# v4_Controller_PCB.net
KiCad netlist of a schematic drawn in EAGLE
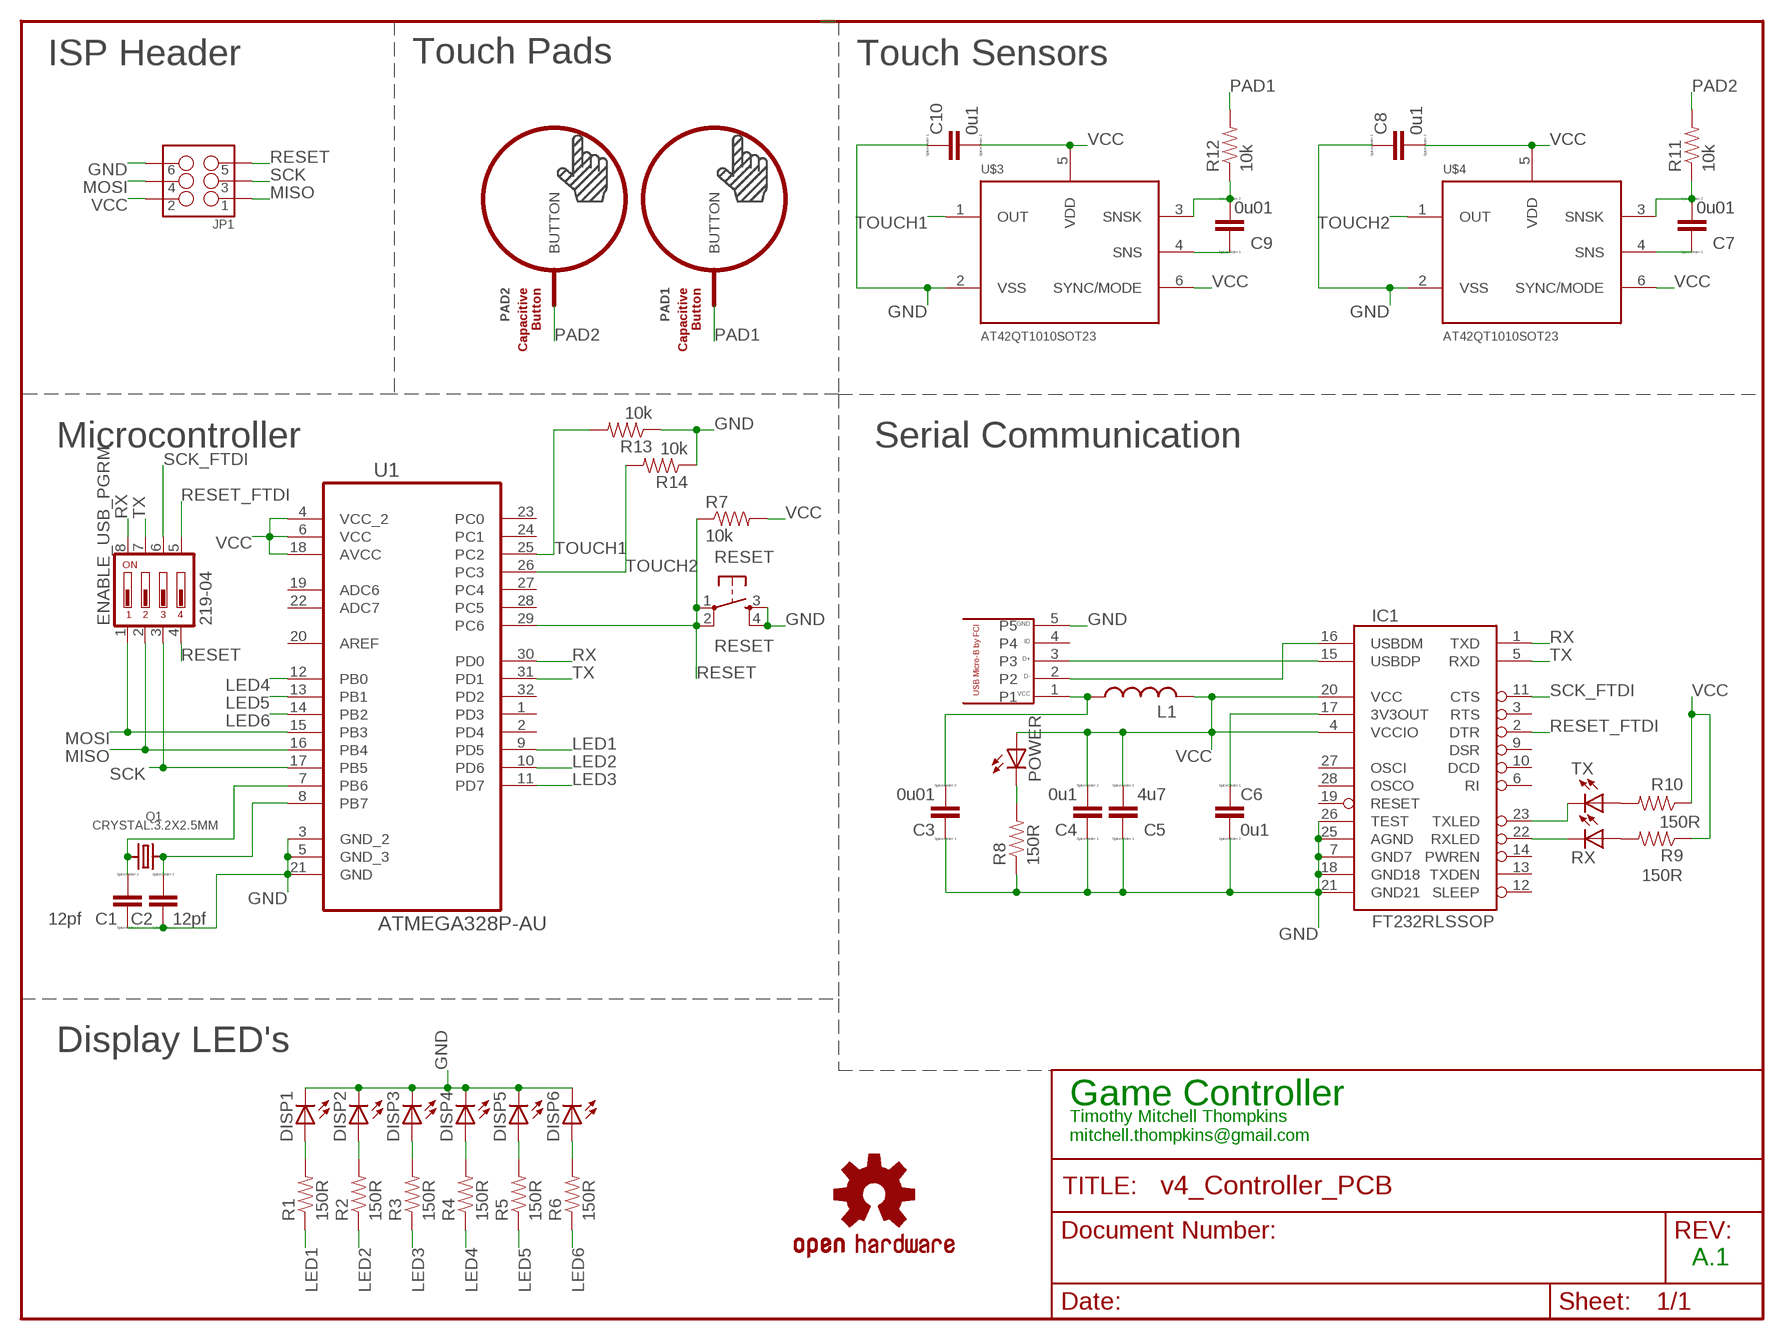
[diagram p0: schematic, sheet 1]

(export (version "E")
  (design (tool "Eeschema 10.0.6"))
  (components
    (comp (ref "BUTTON1")
      (value "TOUCH_LOGO")
      (footprint "eagle-import:TOUCH_LOGO")
      (libsource (lib "eagle-import") (part "TOUCH_LOGO"))
    )
    (comp (ref "C1")
      (value "12pf")
      (footprint "eagle-import:C0603")
      (libsource (lib "eagle-import") (part "CC0603"))
    )
    (comp (ref "C2")
      (value "12pf")
      (footprint "eagle-import:C0603")
      (libsource (lib "eagle-import") (part "CC0603"))
    )
    (comp (ref "C3")
      (value "0u01")
      (footprint "eagle-import:C0603")
      (libsource (lib "eagle-import") (part "CC0603"))
    )
    (comp (ref "C4")
      (value "0u1")
      (footprint "eagle-import:C0603")
      (libsource (lib "eagle-import") (part "CC0603"))
    )
    (comp (ref "C5")
      (value "4u7")
      (footprint "eagle-import:C0603")
      (libsource (lib "eagle-import") (part "CC0603"))
    )
    (comp (ref "C6")
      (value "0u1")
      (footprint "eagle-import:C0603")
      (libsource (lib "eagle-import") (part "CC0603"))
    )
    (comp (ref "C7")
      (value "0u01")
      (footprint "eagle-import:C0603")
      (libsource (lib "eagle-import") (part "CC0603"))
    )
    (comp (ref "C8")
      (value "0u1")
      (footprint "eagle-import:C0603")
      (libsource (lib "eagle-import") (part "CC0603"))
    )
    (comp (ref "C9")
      (value "0u01")
      (footprint "eagle-import:C0603")
      (libsource (lib "eagle-import") (part "CC0603"))
    )
    (comp (ref "C10")
      (value "0u1")
      (footprint "eagle-import:C0603")
      (libsource (lib "eagle-import") (part "CC0603"))
    )
    (comp (ref "DISP1")
      (value "LEDCHIPLED_0603")
      (footprint "eagle-import:CHIPLED_0603")
      (libsource (lib "eagle-import") (part "LEDCHIPLED_0603"))
    )
    (comp (ref "DISP2")
      (value "LEDCHIPLED_0603")
      (footprint "eagle-import:CHIPLED_0603")
      (libsource (lib "eagle-import") (part "LEDCHIPLED_0603"))
    )
    (comp (ref "DISP3")
      (value "LEDCHIPLED_0603")
      (footprint "eagle-import:CHIPLED_0603")
      (libsource (lib "eagle-import") (part "LEDCHIPLED_0603"))
    )
    (comp (ref "DISP4")
      (value "LEDCHIPLED_0603")
      (footprint "eagle-import:CHIPLED_0603")
      (libsource (lib "eagle-import") (part "LEDCHIPLED_0603"))
    )
    (comp (ref "DISP5")
      (value "LEDCHIPLED_0603")
      (footprint "eagle-import:CHIPLED_0603")
      (libsource (lib "eagle-import") (part "LEDCHIPLED_0603"))
    )
    (comp (ref "DISP6")
      (value "LEDCHIPLED_0603")
      (footprint "eagle-import:CHIPLED_0603")
      (libsource (lib "eagle-import") (part "LEDCHIPLED_0603"))
    )
    (comp (ref "ENABLE_USB_PGRM")
      (value "219-04")
      (footprint "eagle-import:CTS-219-04")
      (libsource (lib "eagle-import") (part "219-04"))
    )
    (comp (ref "IC1")
      (value "FT232RLSSOP")
      (footprint "eagle-import:SSOP28DB")
      (libsource (lib "eagle-import") (part "FT232RLSSOP"))
    )
    (comp (ref "JP1")
      (value "M03X2POGO_PINS")
      (footprint "eagle-import:2X3_POGO")
      (libsource (lib "eagle-import") (part "M03X2POGO_PINS"))
    )
    (comp (ref "L1")
      (value "L-USL2012C")
      (footprint "eagle-import:L2012C")
      (libsource (lib "eagle-import") (part "L-USL2012C"))
    )
    (comp (ref "LOGO2")
      (value "OSHW-LOGOS")
      (footprint "eagle-import:OSHW-LOGO-S")
      (libsource (lib "eagle-import") (part "OSHW-LOGOS"))
    )
    (comp (ref "PAD1")
      (value "BUTTON_PASSIVE8MM")
      (footprint "eagle-import:BUTTON_PASSIVE_8MM")
      (libsource (lib "eagle-import") (part "BUTTON_PASSIVE8MM"))
    )
    (comp (ref "PAD2")
      (value "BUTTON_PASSIVE8MM")
      (footprint "eagle-import:BUTTON_PASSIVE_8MM")
      (libsource (lib "eagle-import") (part "BUTTON_PASSIVE8MM"))
    )
    (comp (ref "POWER")
      (value "LEDCHIPLED_0603")
      (footprint "eagle-import:CHIPLED_0603")
      (libsource (lib "eagle-import") (part "LEDCHIPLED_0603"))
    )
    (comp (ref "Q1")
      (value "CRYSTAL.3.2X2.5MM")
      (footprint "eagle-import:3.2X2.5MM")
      (libsource (lib "eagle-import") (part "CRYSTAL.3.2X2.5MM"))
    )
    (comp (ref "R1")
      (value "150R")
      (footprint "eagle-import:0603-RES")
      (libsource (lib "eagle-import") (part "RESISTOR0603-RES"))
    )
    (comp (ref "R2")
      (value "150R")
      (footprint "eagle-import:0603-RES")
      (libsource (lib "eagle-import") (part "RESISTOR0603-RES"))
    )
    (comp (ref "R3")
      (value "150R")
      (footprint "eagle-import:0603-RES")
      (libsource (lib "eagle-import") (part "RESISTOR0603-RES"))
    )
    (comp (ref "R4")
      (value "150R")
      (footprint "eagle-import:0603-RES")
      (libsource (lib "eagle-import") (part "RESISTOR0603-RES"))
    )
    (comp (ref "R5")
      (value "150R")
      (footprint "eagle-import:0603-RES")
      (libsource (lib "eagle-import") (part "RESISTOR0603-RES"))
    )
    (comp (ref "R6")
      (value "150R")
      (footprint "eagle-import:0603-RES")
      (libsource (lib "eagle-import") (part "RESISTOR0603-RES"))
    )
    (comp (ref "R7")
      (value "10k")
      (footprint "eagle-import:0603-RES")
      (libsource (lib "eagle-import") (part "RESISTOR0603-RES"))
    )
    (comp (ref "R8")
      (value "150R")
      (footprint "eagle-import:0603-RES")
      (libsource (lib "eagle-import") (part "RESISTOR0603-RES"))
    )
    (comp (ref "R9")
      (value "150R")
      (footprint "eagle-import:0603-RES")
      (libsource (lib "eagle-import") (part "RESISTOR0603-RES"))
    )
    (comp (ref "R10")
      (value "150R")
      (footprint "eagle-import:0603-RES")
      (libsource (lib "eagle-import") (part "RESISTOR0603-RES"))
    )
    (comp (ref "R11")
      (value "10k")
      (footprint "eagle-import:0603-RES")
      (libsource (lib "eagle-import") (part "RESISTOR0603-RES"))
    )
    (comp (ref "R12")
      (value "10k")
      (footprint "eagle-import:0603-RES")
      (libsource (lib "eagle-import") (part "RESISTOR0603-RES"))
    )
    (comp (ref "R13")
      (value "10k")
      (footprint "eagle-import:0603-RES")
      (libsource (lib "eagle-import") (part "RESISTOR0603-RES"))
    )
    (comp (ref "R14")
      (value "10k")
      (footprint "eagle-import:0603-RES")
      (libsource (lib "eagle-import") (part "RESISTOR0603-RES"))
    )
    (comp (ref "RESET")
      (value "RESET")
      (footprint "eagle-import:TACTILE-PTH")
      (libsource (lib "eagle-import") (part "TAC_SWITCHPTH"))
    )
    (comp (ref "RX")
      (value "LEDCHIPLED_0603")
      (footprint "eagle-import:CHIPLED_0603")
      (libsource (lib "eagle-import") (part "LEDCHIPLED_0603"))
    )
    (comp (ref "TX")
      (value "LEDCHIPLED_0603")
      (footprint "eagle-import:CHIPLED_0603")
      (libsource (lib "eagle-import") (part "LEDCHIPLED_0603"))
    )
    (comp (ref "U$1")
      (value "USB_MICRO_B_FCI")
      (footprint "eagle-import:10118194-0001LF")
      (libsource (lib "eagle-import") (part "USB_MICRO_B_FCI"))
    )
    (comp (ref "U$3")
      (value "AT42QT1010SOT23")
      (footprint "eagle-import:SOT23-6")
      (libsource (lib "eagle-import") (part "AT42QT1010SOT23"))
    )
    (comp (ref "U$4")
      (value "AT42QT1010SOT23")
      (footprint "eagle-import:SOT23-6")
      (libsource (lib "eagle-import") (part "AT42QT1010SOT23"))
    )
    (comp (ref "U$6")
      (value "TOUCH_LOGO")
      (footprint "eagle-import:TOUCH_LOGO")
      (libsource (lib "eagle-import") (part "TOUCH_LOGO"))
    )
    (comp (ref "U1")
      (value "ATMEGA328P-AU")
      (footprint "eagle-import:QFP80P900X900X120-32N")
      (libsource (lib "eagle-import") (part "ATMEGA328P-AU"))
    )
  )
  (nets
    (net (code "1") (name "/GND") (class "Default")
      (node (ref "C1") (pin "1") (pinfunction "1_1") (pintype "passive"))
      (node (ref "C10") (pin "1") (pinfunction "1_1") (pintype "passive"))
      (node (ref "C2") (pin "1") (pinfunction "1_1") (pintype "passive"))
      (node (ref "C3") (pin "1") (pinfunction "1_1") (pintype "passive"))
      (node (ref "C4") (pin "1") (pinfunction "1_1") (pintype "passive"))
      (node (ref "C5") (pin "1") (pinfunction "1_1") (pintype "passive"))
      (node (ref "C6") (pin "2") (pinfunction "2_2") (pintype "passive"))
      (node (ref "C8") (pin "1") (pinfunction "1_1") (pintype "passive"))
      (node (ref "DISP1") (pin "C") (pinfunction "C_C") (pintype "passive"))
      (node (ref "DISP2") (pin "C") (pinfunction "C_C") (pintype "passive"))
      (node (ref "DISP3") (pin "C") (pinfunction "C_C") (pintype "passive"))
      (node (ref "DISP4") (pin "C") (pinfunction "C_C") (pintype "passive"))
      (node (ref "DISP5") (pin "C") (pinfunction "C_C") (pintype "passive"))
      (node (ref "DISP6") (pin "C") (pinfunction "C_C") (pintype "passive"))
      (node (ref "IC1") (pin "18") (pinfunction "GND18_18") (pintype "power_in"))
      (node (ref "IC1") (pin "21") (pinfunction "GND21_21") (pintype "power_in"))
      (node (ref "IC1") (pin "25") (pinfunction "AGND_25") (pintype "power_in"))
      (node (ref "IC1") (pin "26") (pinfunction "TEST_26") (pintype "input"))
      (node (ref "IC1") (pin "7") (pinfunction "GND7_7") (pintype "power_in"))
      (node (ref "JP1") (pin "P$6") (pinfunction "6_P$6") (pintype "bidirectional"))
      (node (ref "R13") (pin "1") (pinfunction "1_1") (pintype "passive"))
      (node (ref "R14") (pin "1") (pinfunction "1_1") (pintype "passive"))
      (node (ref "R8") (pin "1") (pinfunction "1_1") (pintype "passive"))
      (node (ref "RESET") (pin "3") (pinfunction "3_3") (pintype "passive"))
      (node (ref "RESET") (pin "4") (pinfunction "4_4") (pintype "passive"))
      (node (ref "U$1") (pin "5") (pinfunction "P5_5") (pintype "passive"))
      (node (ref "U$3") (pin "2") (pinfunction "VSS_2") (pintype "bidirectional"))
      (node (ref "U$4") (pin "2") (pinfunction "VSS_2") (pintype "bidirectional"))
      (node (ref "U1") (pin "21") (pinfunction "GND_21") (pintype "passive"))
      (node (ref "U1") (pin "3") (pinfunction "GND_2_3") (pintype "passive"))
      (node (ref "U1") (pin "5") (pinfunction "GND_3_5") (pintype "passive"))
    )
    (net (code "2") (name "/LED1") (class "Default")
      (node (ref "R1") (pin "1") (pinfunction "1_1") (pintype "passive"))
      (node (ref "U1") (pin "9") (pinfunction "PD5_9") (pintype "bidirectional"))
    )
    (net (code "3") (name "/LED2") (class "Default")
      (node (ref "R2") (pin "1") (pinfunction "1_1") (pintype "passive"))
      (node (ref "U1") (pin "10") (pinfunction "PD6_10") (pintype "bidirectional"))
    )
    (net (code "4") (name "/LED3") (class "Default")
      (node (ref "R3") (pin "1") (pinfunction "1_1") (pintype "passive"))
      (node (ref "U1") (pin "11") (pinfunction "PD7_11") (pintype "bidirectional"))
    )
    (net (code "5") (name "/LED4") (class "Default")
      (node (ref "R4") (pin "1") (pinfunction "1_1") (pintype "passive"))
      (node (ref "U1") (pin "12") (pinfunction "PB0_12") (pintype "bidirectional"))
    )
    (net (code "6") (name "/LED5") (class "Default")
      (node (ref "R5") (pin "1") (pinfunction "1_1") (pintype "passive"))
      (node (ref "U1") (pin "13") (pinfunction "PB1_13") (pintype "bidirectional"))
    )
    (net (code "7") (name "/LED6") (class "Default")
      (node (ref "R6") (pin "1") (pinfunction "1_1") (pintype "passive"))
      (node (ref "U1") (pin "14") (pinfunction "PB2_14") (pintype "bidirectional"))
    )
    (net (code "8") (name "/MISO") (class "Default")
      (node (ref "ENABLE_USB_PGRM") (pin "2") (pinfunction "2_2") (pintype "passive"))
      (node (ref "JP1") (pin "P$1") (pinfunction "1_P$1") (pintype "bidirectional"))
      (node (ref "U1") (pin "16") (pinfunction "PB4_16") (pintype "bidirectional"))
    )
    (net (code "9") (name "/MOSI") (class "Default")
      (node (ref "ENABLE_USB_PGRM") (pin "1") (pinfunction "1_1") (pintype "passive"))
      (node (ref "JP1") (pin "P$4") (pinfunction "4_P$4") (pintype "bidirectional"))
      (node (ref "U1") (pin "15") (pinfunction "PB3_15") (pintype "bidirectional"))
    )
    (net (code "10") (name "/PAD1") (class "Default")
      (node (ref "PAD1") (pin "P$1") (pinfunction "BUTTON_P$1") (pintype "passive"))
      (node (ref "R12") (pin "2") (pinfunction "2_2") (pintype "passive"))
    )
    (net (code "11") (name "/PAD2") (class "Default")
      (node (ref "PAD2") (pin "P$1") (pinfunction "BUTTON_P$1") (pintype "passive"))
      (node (ref "R11") (pin "2") (pinfunction "2_2") (pintype "passive"))
    )
    (net (code "12") (name "/RESET") (class "Default")
      (node (ref "ENABLE_USB_PGRM") (pin "4") (pinfunction "4_4") (pintype "passive"))
      (node (ref "JP1") (pin "P$5") (pinfunction "5_P$5") (pintype "bidirectional"))
      (node (ref "R7") (pin "1") (pinfunction "1_1") (pintype "passive"))
      (node (ref "RESET") (pin "1") (pinfunction "1_1") (pintype "passive"))
      (node (ref "RESET") (pin "2") (pinfunction "2_2") (pintype "passive"))
      (node (ref "U1") (pin "29") (pinfunction "PC6_29") (pintype "bidirectional"))
    )
    (net (code "13") (name "/RESET_FTDI") (class "Default")
      (node (ref "ENABLE_USB_PGRM") (pin "5") (pinfunction "5_5") (pintype "passive"))
      (node (ref "IC1") (pin "2") (pinfunction "DTR_2") (pintype "output"))
    )
    (net (code "14") (name "/RX") (class "Default")
      (node (ref "ENABLE_USB_PGRM") (pin "8") (pinfunction "8_8") (pintype "passive"))
      (node (ref "IC1") (pin "1") (pinfunction "TXD_1") (pintype "output"))
      (node (ref "U1") (pin "30") (pinfunction "PD0_30") (pintype "bidirectional"))
    )
    (net (code "15") (name "/SCK") (class "Default")
      (node (ref "ENABLE_USB_PGRM") (pin "3") (pinfunction "3_3") (pintype "passive"))
      (node (ref "JP1") (pin "P$3") (pinfunction "3_P$3") (pintype "bidirectional"))
      (node (ref "U1") (pin "17") (pinfunction "PB5_17") (pintype "bidirectional"))
    )
    (net (code "16") (name "/SCK_FTDI") (class "Default")
      (node (ref "ENABLE_USB_PGRM") (pin "6") (pinfunction "6_6") (pintype "passive"))
      (node (ref "IC1") (pin "11") (pinfunction "CTS_11") (pintype "input"))
    )
    (net (code "17") (name "/TOUCH1") (class "Default")
      (node (ref "R13") (pin "2") (pinfunction "2_2") (pintype "passive"))
      (node (ref "U$3") (pin "1") (pinfunction "OUT_1") (pintype "bidirectional"))
      (node (ref "U1") (pin "25") (pinfunction "PC2_25") (pintype "bidirectional"))
    )
    (net (code "18") (name "/TOUCH2") (class "Default")
      (node (ref "R14") (pin "2") (pinfunction "2_2") (pintype "passive"))
      (node (ref "U$4") (pin "1") (pinfunction "OUT_1") (pintype "bidirectional"))
      (node (ref "U1") (pin "26") (pinfunction "PC3_26") (pintype "bidirectional"))
    )
    (net (code "19") (name "/TX") (class "Default")
      (node (ref "ENABLE_USB_PGRM") (pin "7") (pinfunction "7_7") (pintype "passive"))
      (node (ref "IC1") (pin "5") (pinfunction "RXD_5") (pintype "input"))
      (node (ref "U1") (pin "31") (pinfunction "PD1_31") (pintype "bidirectional"))
    )
    (net (code "20") (name "/VCC") (class "Default")
      (node (ref "C10") (pin "2") (pinfunction "2_2") (pintype "passive"))
      (node (ref "C4") (pin "2") (pinfunction "2_2") (pintype "passive"))
      (node (ref "C5") (pin "2") (pinfunction "2_2") (pintype "passive"))
      (node (ref "C8") (pin "2") (pinfunction "2_2") (pintype "passive"))
      (node (ref "IC1") (pin "20") (pinfunction "VCC_20") (pintype "power_in"))
      (node (ref "IC1") (pin "4") (pinfunction "VCCIO_4") (pintype "power_in"))
      (node (ref "JP1") (pin "P$2") (pinfunction "2_P$2") (pintype "bidirectional"))
      (node (ref "L1") (pin "2") (pinfunction "2_2") (pintype "passive"))
      (node (ref "POWER") (pin "A") (pinfunction "A_A") (pintype "passive"))
      (node (ref "R10") (pin "1") (pinfunction "1_1") (pintype "passive"))
      (node (ref "R7") (pin "2") (pinfunction "2_2") (pintype "passive"))
      (node (ref "R9") (pin "1") (pinfunction "1_1") (pintype "passive"))
      (node (ref "U$3") (pin "5") (pinfunction "VDD_5") (pintype "bidirectional"))
      (node (ref "U$3") (pin "6") (pinfunction "SYNC/MODE_6") (pintype "bidirectional"))
      (node (ref "U$4") (pin "5") (pinfunction "VDD_5") (pintype "bidirectional"))
      (node (ref "U$4") (pin "6") (pinfunction "SYNC/MODE_6") (pintype "bidirectional"))
      (node (ref "U1") (pin "18") (pinfunction "AVCC_18") (pintype "power_in"))
      (node (ref "U1") (pin "4") (pinfunction "VCC_2_4") (pintype "power_in"))
      (node (ref "U1") (pin "6") (pinfunction "VCC_6") (pintype "power_in"))
    )
    (net (code "21") (name "Net-(DISP1-PadA)") (class "Default")
      (node (ref "DISP1") (pin "A") (pinfunction "A_A") (pintype "passive"))
      (node (ref "R1") (pin "2") (pinfunction "2_2") (pintype "passive"))
    )
    (net (code "22") (name "Net-(DISP2-PadA)") (class "Default")
      (node (ref "DISP2") (pin "A") (pinfunction "A_A") (pintype "passive"))
      (node (ref "R2") (pin "2") (pinfunction "2_2") (pintype "passive"))
    )
    (net (code "23") (name "Net-(DISP3-PadA)") (class "Default")
      (node (ref "DISP3") (pin "A") (pinfunction "A_A") (pintype "passive"))
      (node (ref "R3") (pin "2") (pinfunction "2_2") (pintype "passive"))
    )
    (net (code "24") (name "Net-(DISP4-PadA)") (class "Default")
      (node (ref "DISP4") (pin "A") (pinfunction "A_A") (pintype "passive"))
      (node (ref "R4") (pin "2") (pinfunction "2_2") (pintype "passive"))
    )
    (net (code "25") (name "Net-(DISP5-PadA)") (class "Default")
      (node (ref "DISP5") (pin "A") (pinfunction "A_A") (pintype "passive"))
      (node (ref "R5") (pin "2") (pinfunction "2_2") (pintype "passive"))
    )
    (net (code "26") (name "Net-(DISP6-PadA)") (class "Default")
      (node (ref "DISP6") (pin "A") (pinfunction "A_A") (pintype "passive"))
      (node (ref "R6") (pin "2") (pinfunction "2_2") (pintype "passive"))
    )
    (net (code "27") (name "Net-(IC1-3V3OUT)") (class "Default")
      (node (ref "C6") (pin "1") (pinfunction "1_1") (pintype "passive"))
      (node (ref "IC1") (pin "17") (pinfunction "3V3OUT_17") (pintype "output"))
    )
    (net (code "28") (name "Net-(IC1-RXLED)") (class "Default")
      (node (ref "IC1") (pin "22") (pinfunction "RXLED_22") (pintype "input"))
      (node (ref "RX") (pin "C") (pinfunction "C_C") (pintype "passive"))
    )
    (net (code "29") (name "Net-(IC1-TXLED)") (class "Default")
      (node (ref "IC1") (pin "23") (pinfunction "TXLED_23") (pintype "input"))
      (node (ref "TX") (pin "C") (pinfunction "C_C") (pintype "passive"))
    )
    (net (code "30") (name "Net-(IC1-USBDM)") (class "Default")
      (node (ref "IC1") (pin "16") (pinfunction "USBDM_16") (pintype "bidirectional"))
      (node (ref "U$1") (pin "2") (pinfunction "P2_2") (pintype "bidirectional"))
    )
    (net (code "31") (name "Net-(IC1-USBDP)") (class "Default")
      (node (ref "IC1") (pin "15") (pinfunction "USBDP_15") (pintype "bidirectional"))
      (node (ref "U$1") (pin "3") (pinfunction "P3_3") (pintype "bidirectional"))
    )
    (net (code "32") (name "Net-(POWER-PadC)") (class "Default")
      (node (ref "POWER") (pin "C") (pinfunction "C_C") (pintype "passive"))
      (node (ref "R8") (pin "2") (pinfunction "2_2") (pintype "passive"))
    )
    (net (code "33") (name "Net-(R9-Pad2)") (class "Default")
      (node (ref "R9") (pin "2") (pinfunction "2_2") (pintype "passive"))
      (node (ref "RX") (pin "A") (pinfunction "A_A") (pintype "passive"))
    )
    (net (code "34") (name "Net-(R10-Pad2)") (class "Default")
      (node (ref "R10") (pin "2") (pinfunction "2_2") (pintype "passive"))
      (node (ref "TX") (pin "A") (pinfunction "A_A") (pintype "passive"))
    )
    (net (code "35") (name "Net-(U$1A-P1)") (class "Default")
      (node (ref "C3") (pin "2") (pinfunction "2_2") (pintype "passive"))
      (node (ref "L1") (pin "1") (pinfunction "1_1") (pintype "passive"))
      (node (ref "U$1") (pin "1") (pinfunction "P1_1") (pintype "power_in"))
    )
    (net (code "36") (name "Net-(U$3-SNS)") (class "Default")
      (node (ref "C9") (pin "1") (pinfunction "1_1") (pintype "passive"))
      (node (ref "U$3") (pin "4") (pinfunction "SNS_4") (pintype "bidirectional"))
    )
    (net (code "37") (name "Net-(U$3-SNSK)") (class "Default")
      (node (ref "C9") (pin "2") (pinfunction "2_2") (pintype "passive"))
      (node (ref "R12") (pin "1") (pinfunction "1_1") (pintype "passive"))
      (node (ref "U$3") (pin "3") (pinfunction "SNSK_3") (pintype "bidirectional"))
    )
    (net (code "38") (name "Net-(U$4-SNS)") (class "Default")
      (node (ref "C7") (pin "1") (pinfunction "1_1") (pintype "passive"))
      (node (ref "U$4") (pin "4") (pinfunction "SNS_4") (pintype "bidirectional"))
    )
    (net (code "39") (name "Net-(U$4-SNSK)") (class "Default")
      (node (ref "C7") (pin "2") (pinfunction "2_2") (pintype "passive"))
      (node (ref "R11") (pin "1") (pinfunction "1_1") (pintype "passive"))
      (node (ref "U$4") (pin "3") (pinfunction "SNSK_3") (pintype "bidirectional"))
    )
    (net (code "40") (name "Net-(U1-PB6)") (class "Default")
      (node (ref "C1") (pin "2") (pinfunction "2_2") (pintype "passive"))
      (node (ref "Q1") (pin "1") (pinfunction "1_1") (pintype "passive"))
      (node (ref "U1") (pin "7") (pinfunction "PB6_7") (pintype "bidirectional"))
    )
    (net (code "41") (name "Net-(U1-PB7)") (class "Default")
      (node (ref "C2") (pin "2") (pinfunction "2_2") (pintype "passive"))
      (node (ref "Q1") (pin "3") (pinfunction "3_3") (pintype "passive"))
      (node (ref "U1") (pin "8") (pinfunction "PB7_8") (pintype "bidirectional"))
    )
    (net (code "42") (name "unconnected-(IC1-DCD-Pad10)") (class "Default")
      (node (ref "IC1") (pin "10") (pinfunction "DCD_10") (pintype "input"))
    )
    (net (code "43") (name "unconnected-(IC1-DSR-Pad9)") (class "Default")
      (node (ref "IC1") (pin "9") (pinfunction "DSR_9") (pintype "input"))
    )
    (net (code "44") (name "unconnected-(IC1-OSCI-Pad27)") (class "Default")
      (node (ref "IC1") (pin "27") (pinfunction "OSCI_27") (pintype "input"))
    )
    (net (code "45") (name "unconnected-(IC1-OSCO-Pad28)") (class "Default")
      (node (ref "IC1") (pin "28") (pinfunction "OSCO_28") (pintype "output"))
    )
    (net (code "46") (name "unconnected-(IC1-PWREN-Pad14)") (class "Default")
      (node (ref "IC1") (pin "14") (pinfunction "PWREN_14") (pintype "input"))
    )
    (net (code "47") (name "unconnected-(IC1-RESET-Pad19)") (class "Default")
      (node (ref "IC1") (pin "19") (pinfunction "RESET_19") (pintype "input"))
    )
    (net (code "48") (name "unconnected-(IC1-RI-Pad6)") (class "Default")
      (node (ref "IC1") (pin "6") (pinfunction "RI_6") (pintype "input"))
    )
    (net (code "49") (name "unconnected-(IC1-RTS-Pad3)") (class "Default")
      (node (ref "IC1") (pin "3") (pinfunction "RTS_3") (pintype "output"))
    )
    (net (code "50") (name "unconnected-(IC1-SLEEP-Pad12)") (class "Default")
      (node (ref "IC1") (pin "12") (pinfunction "SLEEP_12") (pintype "input"))
    )
    (net (code "51") (name "unconnected-(IC1-TXDEN-Pad13)") (class "Default")
      (node (ref "IC1") (pin "13") (pinfunction "TXDEN_13") (pintype "input"))
    )
    (net (code "52") (name "unconnected-(U$1A-P4-Pad4)") (class "Default")
      (node (ref "U$1") (pin "4") (pinfunction "P4_4") (pintype "bidirectional"))
    )
    (net (code "53") (name "unconnected-(U1-ADC6-Pad19)") (class "Default")
      (node (ref "U1") (pin "19") (pinfunction "ADC6_19") (pintype "input"))
    )
    (net (code "54") (name "unconnected-(U1-ADC7-Pad22)") (class "Default")
      (node (ref "U1") (pin "22") (pinfunction "ADC7_22") (pintype "input"))
    )
    (net (code "55") (name "unconnected-(U1-AREF-Pad20)") (class "Default")
      (node (ref "U1") (pin "20") (pinfunction "AREF_20") (pintype "input"))
    )
    (net (code "56") (name "unconnected-(U1-PC0-Pad23)") (class "Default")
      (node (ref "U1") (pin "23") (pinfunction "PC0_23") (pintype "bidirectional"))
    )
    (net (code "57") (name "unconnected-(U1-PC1-Pad24)") (class "Default")
      (node (ref "U1") (pin "24") (pinfunction "PC1_24") (pintype "bidirectional"))
    )
    (net (code "58") (name "unconnected-(U1-PC4-Pad27)") (class "Default")
      (node (ref "U1") (pin "27") (pinfunction "PC4_27") (pintype "bidirectional"))
    )
    (net (code "59") (name "unconnected-(U1-PC5-Pad28)") (class "Default")
      (node (ref "U1") (pin "28") (pinfunction "PC5_28") (pintype "bidirectional"))
    )
    (net (code "60") (name "unconnected-(U1-PD2-Pad32)") (class "Default")
      (node (ref "U1") (pin "32") (pinfunction "PD2_32") (pintype "bidirectional"))
    )
    (net (code "61") (name "unconnected-(U1-PD3-Pad1)") (class "Default")
      (node (ref "U1") (pin "1") (pinfunction "PD3_1") (pintype "bidirectional"))
    )
    (net (code "62") (name "unconnected-(U1-PD4-Pad2)") (class "Default")
      (node (ref "U1") (pin "2") (pinfunction "PD4_2") (pintype "bidirectional"))
    )
  )
)
